# design_sch.net
KiCad netlist of a schematic drawn in EasyEDA
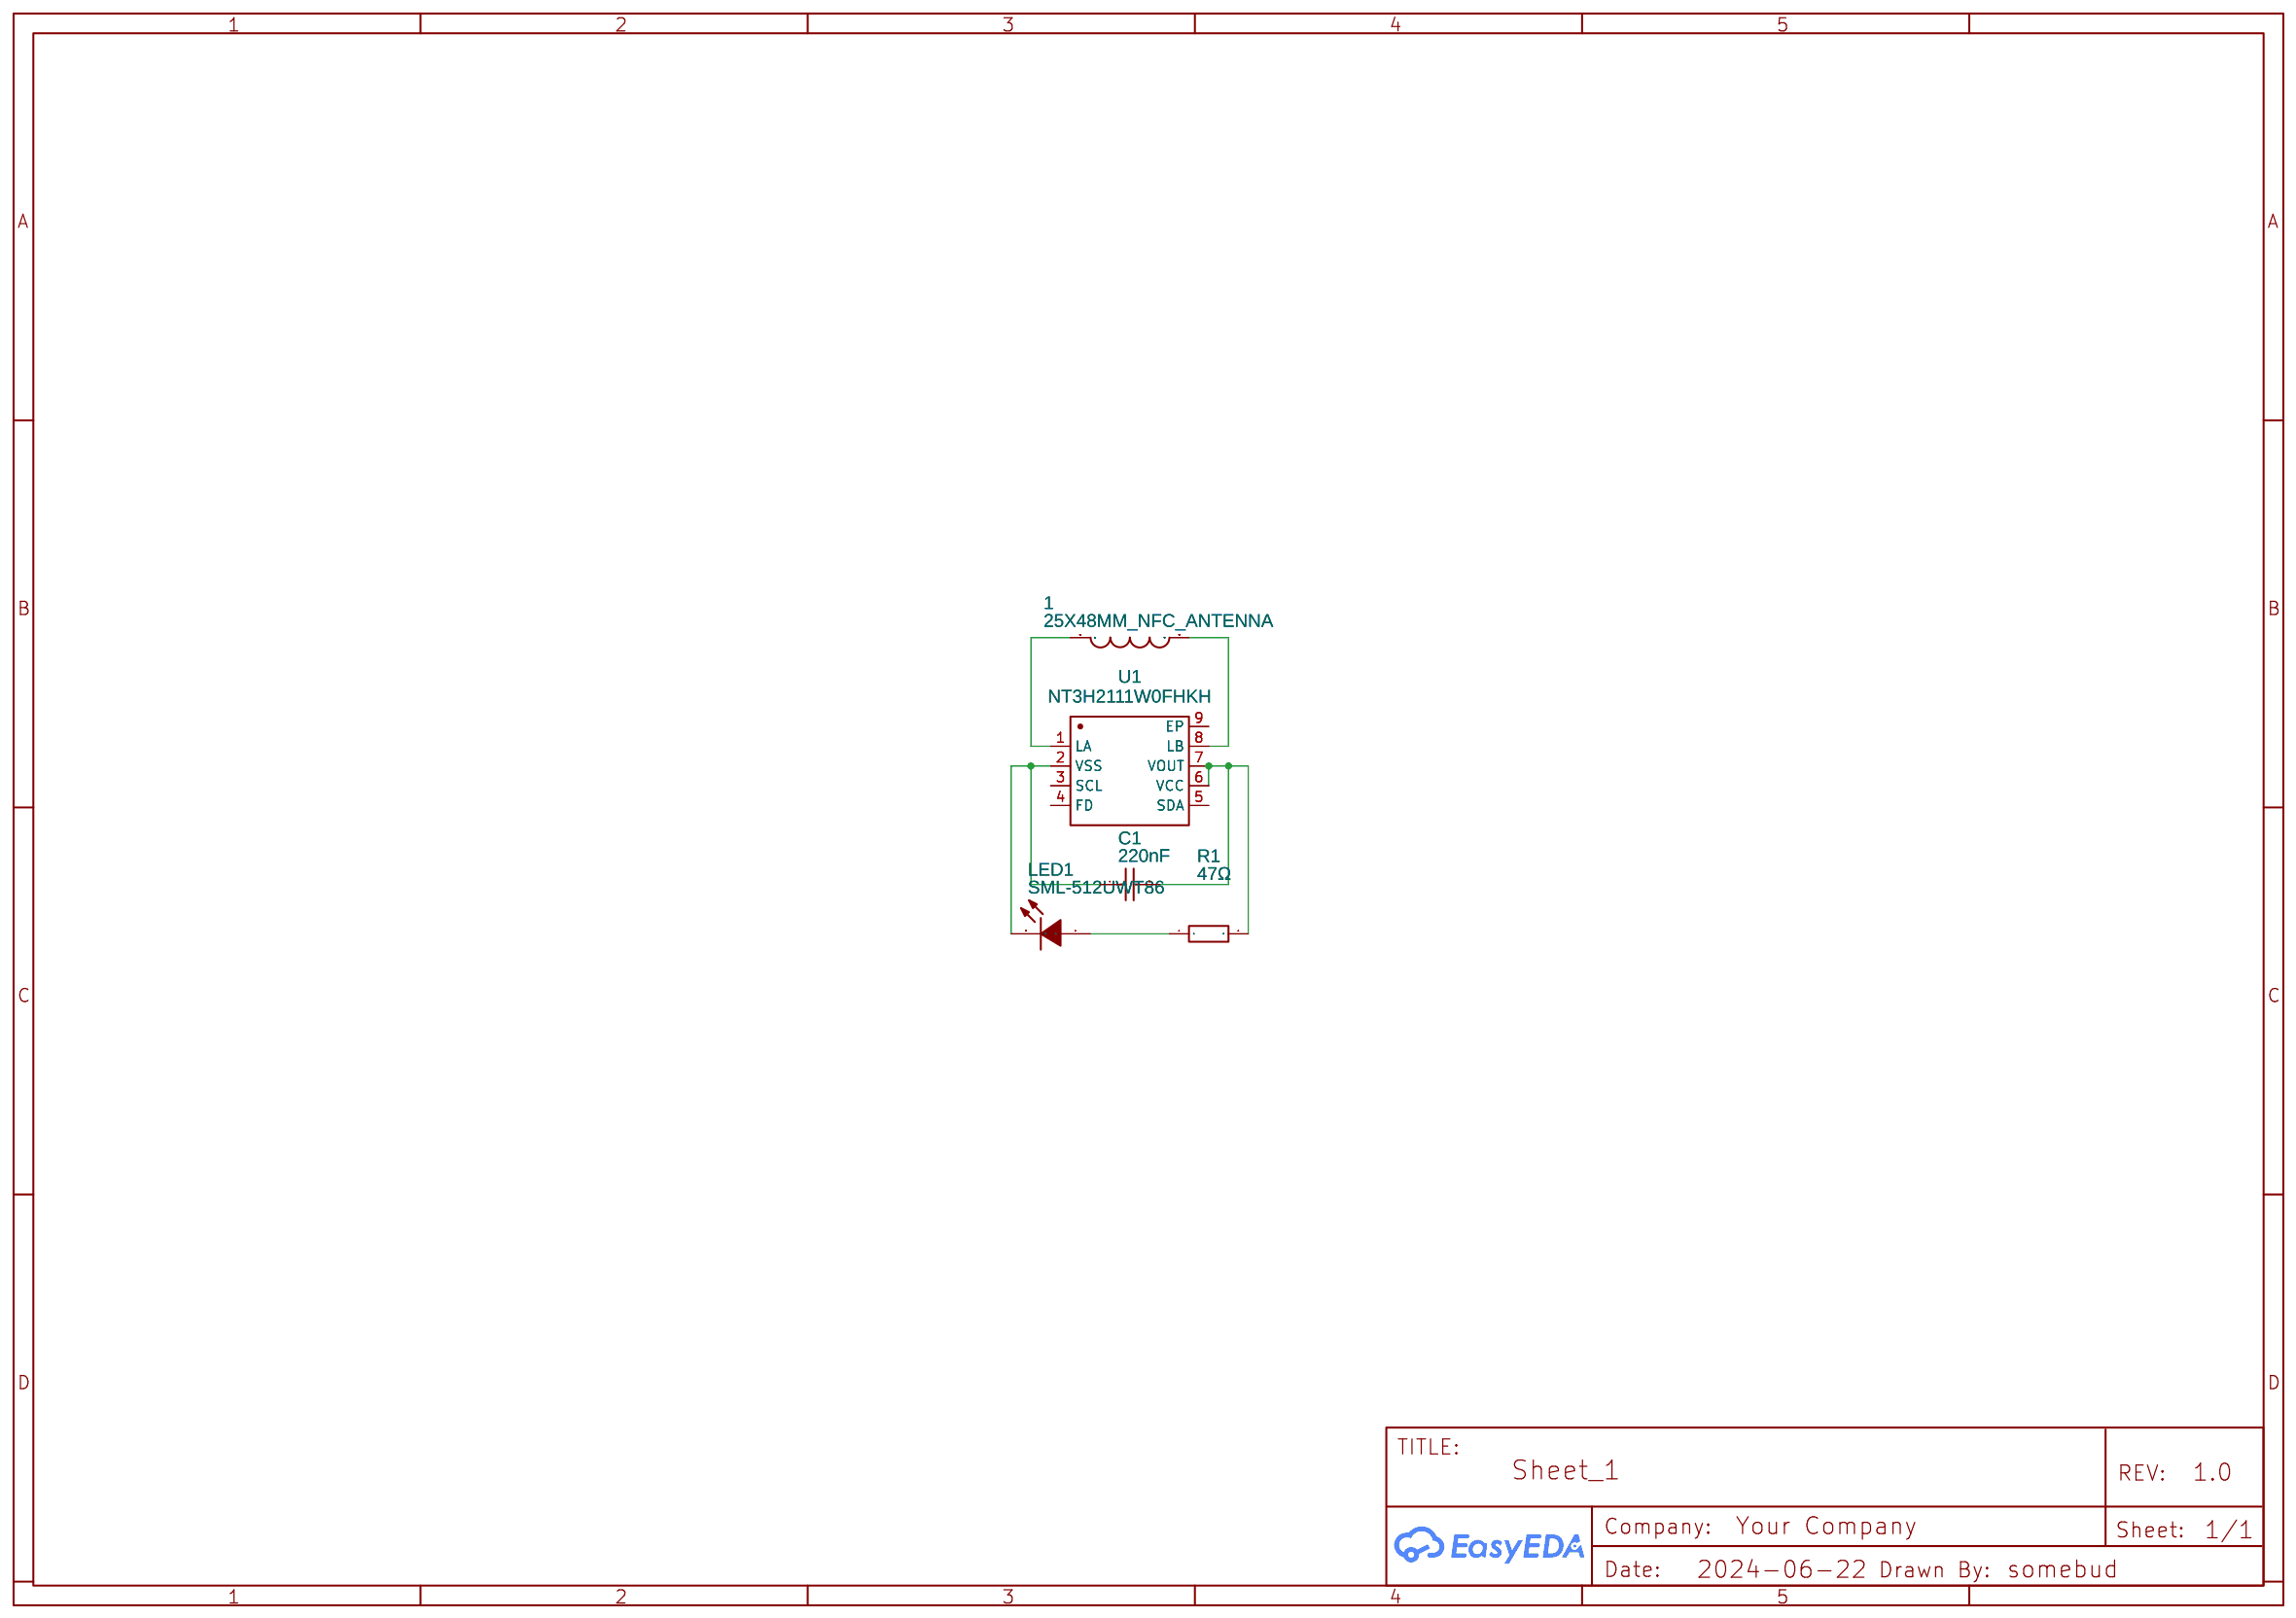
[diagram p0: schematic sheet]

(export (version "E")
  (design (tool "Eeschema 10.0.6"))
  (components
    (comp (ref "1") (value "25X48MM_NFC_ANTENNA") (libsource (lib "") (part "25X48MM_NFC_ANTENNA")))
    (comp (ref "C1")
      (value "220nF")
      (fields
        (field (name "Manufacturer Part") "CL10B224KA8NNNC")
        (field (name "Manufacturer") "SAMSUNG(三星)")
      )
      (libsource (lib "") (part "CL10B224KA8NNNC"))
    )
    (comp (ref "LED1")
      (value "SML-512UWT86")
      (fields (field (name "Manufacturer") "ROHM(罗姆)"))
      (libsource (lib "") (part "SML-512UWT86"))
    )
    (comp (ref "R1")
      (value "47Ω")
      (fields
        (field (name "Manufacturer Part") "0603WAF470JT5E")
        (field (name "Manufacturer") "UNI-ROYAL(厚声)")
      )
      (libsource (lib "") (part "0603WAF470JT5E"))
    )
    (comp (ref "U1")
      (value "NT3H2111W0FHKH")
      (fields (field (name "Manufacturer") "NXP(恩智浦)"))
      (libsource (lib "") (part "NT3H2111W0FHKH"))
    )
  )
  (nets
    (net (code "1") (name "Net-(LED1-A)") (class "Default")
      (node (ref "LED1") (pin "1") (pinfunction "A_1") (pintype "unspecified"))
      (node (ref "R1") (pin "1") (pinfunction "1_1") (pintype "input"))
    )
    (net (code "2") (name "Net-(LED1-K)") (class "Default")
      (node (ref "C1") (pin "1") (pinfunction "1_1") (pintype "input"))
      (node (ref "LED1") (pin "2") (pinfunction "K_2") (pintype "unspecified"))
      (node (ref "U1") (pin "2") (pinfunction "VSS_2") (pintype "unspecified"))
    )
    (net (code "3") (name "Net-(U1-LA)") (class "Default")
      (node (ref "1") (pin "P$2") (pinfunction "P$2_P$2") (pintype "bidirectional"))
      (node (ref "U1") (pin "1") (pinfunction "LA_1") (pintype "unspecified"))
    )
    (net (code "4") (name "Net-(U1-LB)") (class "Default")
      (node (ref "1") (pin "P$1") (pinfunction "P$1_P$1") (pintype "bidirectional"))
      (node (ref "U1") (pin "8") (pinfunction "LB_8") (pintype "unspecified"))
    )
    (net (code "5") (name "Net-(U1-VCC)") (class "Default")
      (node (ref "C1") (pin "2") (pinfunction "2_2") (pintype "input"))
      (node (ref "R1") (pin "2") (pinfunction "2_2") (pintype "input"))
      (node (ref "U1") (pin "6") (pinfunction "VCC_6") (pintype "unspecified"))
      (node (ref "U1") (pin "7") (pinfunction "VOUT_7") (pintype "unspecified"))
    )
    (net (code "6") (name "unconnected-(U1-EP-Pad9)") (class "Default")
      (node (ref "U1") (pin "9") (pinfunction "EP_9") (pintype "unspecified"))
    )
    (net (code "7") (name "unconnected-(U1-FD-Pad4)") (class "Default")
      (node (ref "U1") (pin "4") (pinfunction "FD_4") (pintype "unspecified"))
    )
    (net (code "8") (name "unconnected-(U1-SCL-Pad3)") (class "Default")
      (node (ref "U1") (pin "3") (pinfunction "SCL_3") (pintype "unspecified"))
    )
    (net (code "9") (name "unconnected-(U1-SDA-Pad5)") (class "Default")
      (node (ref "U1") (pin "5") (pinfunction "SDA_5") (pintype "unspecified"))
    )
  )
)
